# EightADC_chnls.net
KiCad netlist of a schematic drawn in Altium Designer
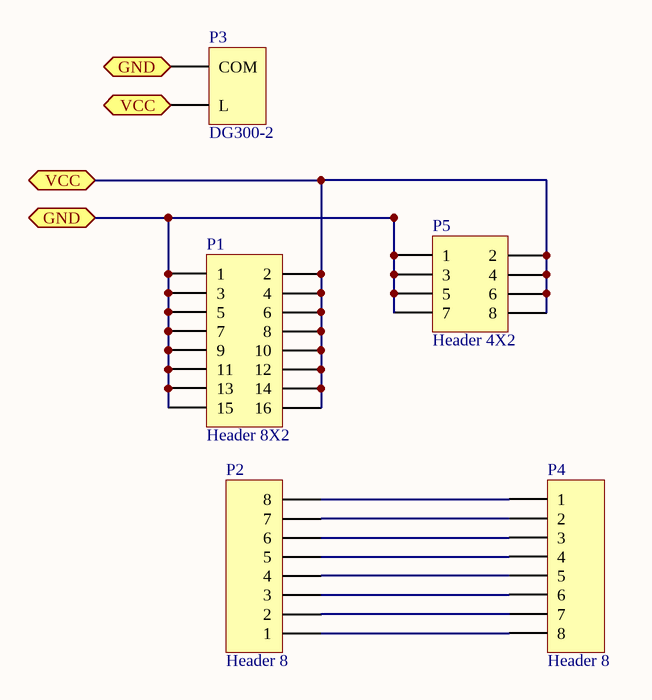
[diagram p0: EightADC_chnls.SchDoc]

(export (version "E")
  (design (tool "Eeschema 10.0.6"))
  (components
    (comp (ref "P1")
      (value "Header 8X2")
      (footprint "HDR2X8")
      (description "Header, 8-Pin, Dual row")
      (fields (field (name "PUBLISHER") "Altium Limited"))
      (libsource (lib "Miscellaneous Connectors") (part "Header 8X2"))
    )
    (comp (ref "P2")
      (value "Header 8")
      (footprint "HDR1X8")
      (description "Header, 8-Pin")
      (fields (field (name "PUBLISHER") "Altium Limited"))
      (libsource (lib "") (part "Header 8_1"))
    )
    (comp (ref "P3")
      (value "DG300-2")
      (footprint "DG300-2")
      (description "Blue contact claws")
      (libsource (lib "MyLib") (part "DG300-2"))
    )
    (comp (ref "P4")
      (value "Header 8")
      (footprint "HDR1X8")
      (description "Header, 8-Pin")
      (fields (field (name "PUBLISHER") "Altium Limited"))
      (libsource (lib "Miscellaneous Connectors") (part "Header 8"))
    )
    (comp (ref "P5")
      (value "Header 4X2")
      (footprint "HDR2X4")
      (description "Header, 4-Pin, Dual row")
      (fields (field (name "PUBLISHER") "Altium Limited"))
      (libsource (lib "Miscellaneous Connectors") (part "Header 4X2"))
    )
  )
  (nets
    (net (code "1") (name "/GND") (class "Default")
      (node (ref "P1") (pin "1") (pinfunction "1_1") (pintype "passive"))
      (node (ref "P1") (pin "11") (pinfunction "11_11") (pintype "passive"))
      (node (ref "P1") (pin "13") (pinfunction "13_13") (pintype "passive"))
      (node (ref "P1") (pin "15") (pinfunction "15_15") (pintype "passive"))
      (node (ref "P1") (pin "3") (pinfunction "3_3") (pintype "passive"))
      (node (ref "P1") (pin "5") (pinfunction "5_5") (pintype "passive"))
      (node (ref "P1") (pin "7") (pinfunction "7_7") (pintype "passive"))
      (node (ref "P1") (pin "9") (pinfunction "9_9") (pintype "passive"))
      (node (ref "P3") (pin "1") (pinfunction "COM_1") (pintype "passive"))
      (node (ref "P5") (pin "1") (pinfunction "1_1") (pintype "passive"))
      (node (ref "P5") (pin "3") (pinfunction "3_3") (pintype "passive"))
      (node (ref "P5") (pin "5") (pinfunction "5_5") (pintype "passive"))
      (node (ref "P5") (pin "7") (pinfunction "7_7") (pintype "passive"))
    )
    (net (code "2") (name "/VCC") (class "Default")
      (node (ref "P1") (pin "10") (pinfunction "10_10") (pintype "passive"))
      (node (ref "P1") (pin "12") (pinfunction "12_12") (pintype "passive"))
      (node (ref "P1") (pin "14") (pinfunction "14_14") (pintype "passive"))
      (node (ref "P1") (pin "16") (pinfunction "16_16") (pintype "passive"))
      (node (ref "P1") (pin "2") (pinfunction "2_2") (pintype "passive"))
      (node (ref "P1") (pin "4") (pinfunction "4_4") (pintype "passive"))
      (node (ref "P1") (pin "6") (pinfunction "6_6") (pintype "passive"))
      (node (ref "P1") (pin "8") (pinfunction "8_8") (pintype "passive"))
      (node (ref "P3") (pin "2") (pinfunction "L_2") (pintype "passive"))
      (node (ref "P5") (pin "2") (pinfunction "2_2") (pintype "passive"))
      (node (ref "P5") (pin "4") (pinfunction "4_4") (pintype "passive"))
      (node (ref "P5") (pin "6") (pinfunction "6_6") (pintype "passive"))
      (node (ref "P5") (pin "8") (pinfunction "8_8") (pintype "passive"))
    )
    (net (code "3") (name "Net-(P2-Pad1)") (class "Default")
      (node (ref "P2") (pin "1") (pinfunction "1_1") (pintype "passive"))
      (node (ref "P4") (pin "8") (pinfunction "8_8") (pintype "passive"))
    )
    (net (code "4") (name "Net-(P2-Pad2)") (class "Default")
      (node (ref "P2") (pin "2") (pinfunction "2_2") (pintype "passive"))
      (node (ref "P4") (pin "7") (pinfunction "7_7") (pintype "passive"))
    )
    (net (code "5") (name "Net-(P2-Pad3)") (class "Default")
      (node (ref "P2") (pin "3") (pinfunction "3_3") (pintype "passive"))
      (node (ref "P4") (pin "6") (pinfunction "6_6") (pintype "passive"))
    )
    (net (code "6") (name "Net-(P2-Pad4)") (class "Default")
      (node (ref "P2") (pin "4") (pinfunction "4_4") (pintype "passive"))
      (node (ref "P4") (pin "5") (pinfunction "5_5") (pintype "passive"))
    )
    (net (code "7") (name "Net-(P2-Pad5)") (class "Default")
      (node (ref "P2") (pin "5") (pinfunction "5_5") (pintype "passive"))
      (node (ref "P4") (pin "4") (pinfunction "4_4") (pintype "passive"))
    )
    (net (code "8") (name "Net-(P2-Pad6)") (class "Default")
      (node (ref "P2") (pin "6") (pinfunction "6_6") (pintype "passive"))
      (node (ref "P4") (pin "3") (pinfunction "3_3") (pintype "passive"))
    )
    (net (code "9") (name "Net-(P2-Pad7)") (class "Default")
      (node (ref "P2") (pin "7") (pinfunction "7_7") (pintype "passive"))
      (node (ref "P4") (pin "2") (pinfunction "2_2") (pintype "passive"))
    )
    (net (code "10") (name "Net-(P2-Pad8)") (class "Default")
      (node (ref "P2") (pin "8") (pinfunction "8_8") (pintype "passive"))
      (node (ref "P4") (pin "1") (pinfunction "1_1") (pintype "passive"))
    )
  )
)
